# Versorgungseinheit_v2.net
KiCad netlist of a schematic drawn in EAGLE
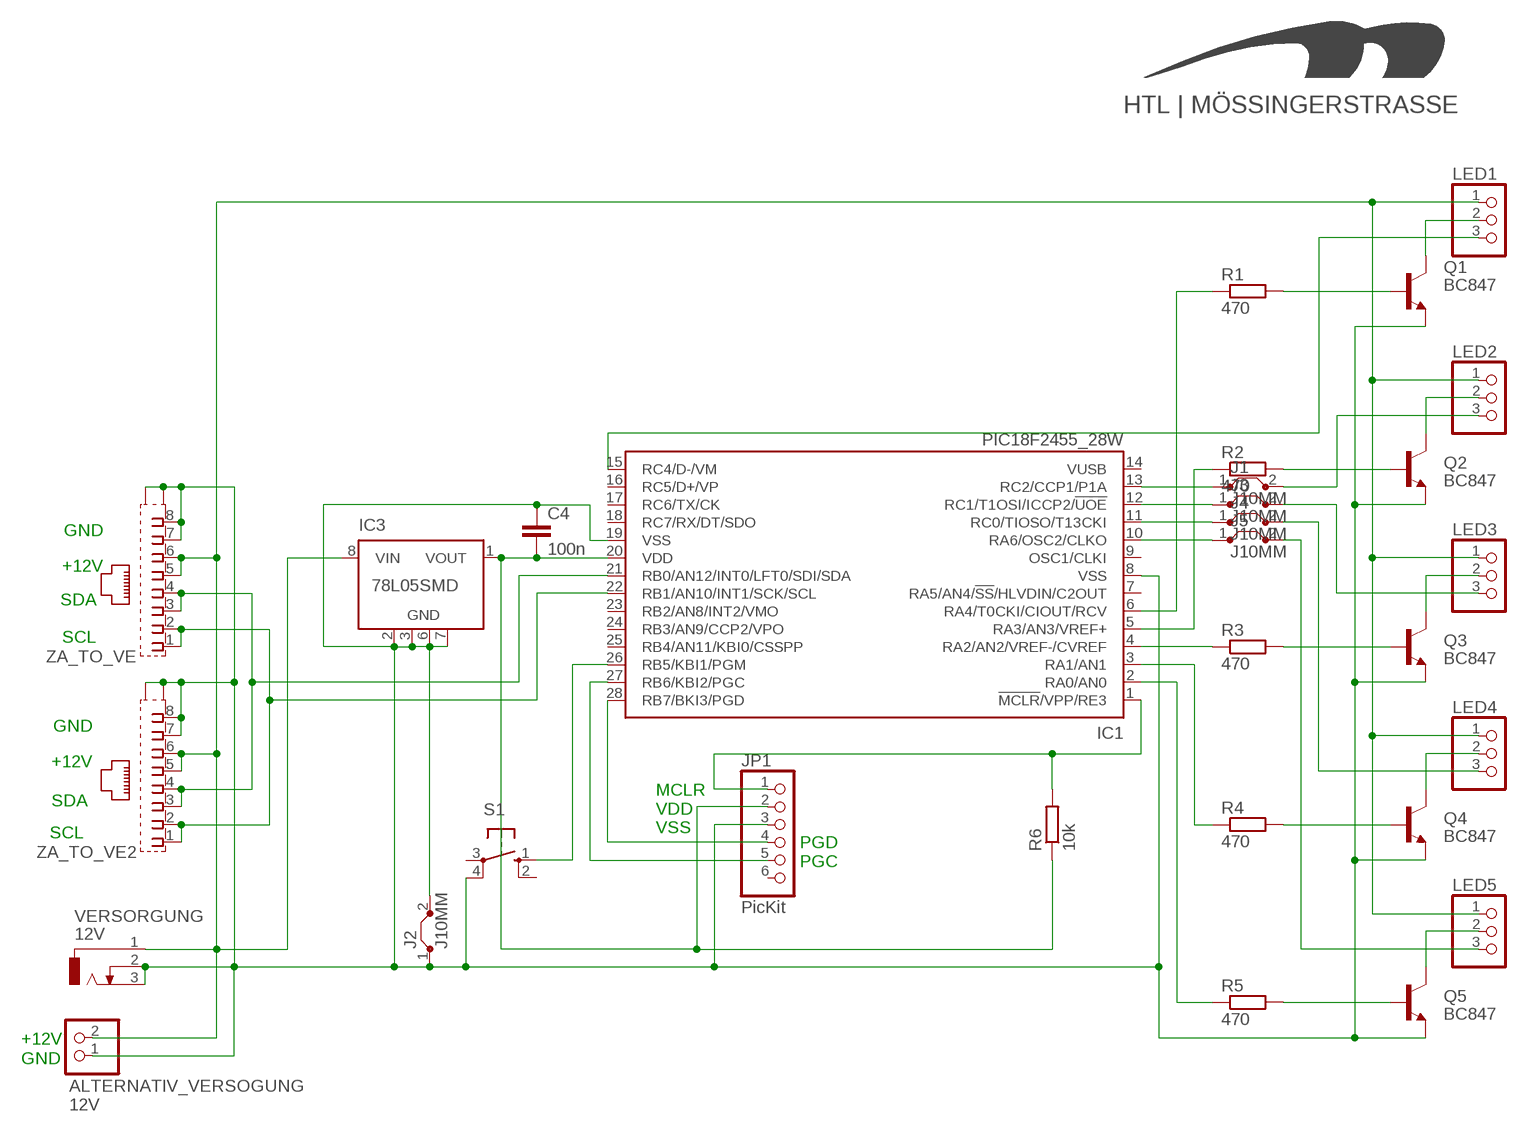
[diagram p0: schematic, sheet 1]

(export (version "E")
  (design (tool "Eeschema 10.0.6"))
  (components
    (comp (ref "ALTERNATIV_VERSOGUNG")
      (value "12V")
      (footprint "eagle-import:1X02")
      (libsource (lib "eagle-import") (part "PINHD-1X2"))
    )
    (comp (ref "C4")
      (value "100n")
      (footprint "eagle-import:C1206")
      (libsource (lib "eagle-import") (part "C-EUC1206"))
    )
    (comp (ref "IC1")
      (value "PIC18F2455_28W")
      (footprint "eagle-import:SO28W")
      (fields (field (name "MF") "MICROCHIP") (field (name "MPN") "PIC18F2455-I/SO"))
      (libsource (lib "eagle-import") (part "PIC18F2_28W455"))
    )
    (comp (ref "IC3")
      (value "78L05SMD")
      (footprint "eagle-import:SO08")
      (libsource (lib "eagle-import") (part "78LSMD05"))
    )
    (comp (ref "J1")
      (value "J10MM")
      (footprint "eagle-import:10")
      (libsource (lib "eagle-import") (part "J10MM"))
    )
    (comp (ref "J2")
      (value "J10MM")
      (footprint "eagle-import:10")
      (libsource (lib "eagle-import") (part "J10MM"))
    )
    (comp (ref "J3")
      (value "J10MM")
      (footprint "eagle-import:10")
      (libsource (lib "eagle-import") (part "J10MM"))
    )
    (comp (ref "J4")
      (value "J10MM")
      (footprint "eagle-import:10")
      (libsource (lib "eagle-import") (part "J10MM"))
    )
    (comp (ref "J5")
      (value "J10MM")
      (footprint "eagle-import:10")
      (libsource (lib "eagle-import") (part "J10MM"))
    )
    (comp (ref "JP1")
      (value "PicKit")
      (footprint "eagle-import:1X06")
      (libsource (lib "eagle-import") (part "PINHD-1X6"))
    )
    (comp (ref "LED1")
      (value "PINHD-1X3")
      (footprint "eagle-import:1X03")
      (libsource (lib "eagle-import") (part "PINHD-1X3"))
    )
    (comp (ref "LED2")
      (value "PINHD-1X3")
      (footprint "eagle-import:1X03")
      (libsource (lib "eagle-import") (part "PINHD-1X3"))
    )
    (comp (ref "LED3")
      (value "PINHD-1X3")
      (footprint "eagle-import:1X03")
      (libsource (lib "eagle-import") (part "PINHD-1X3"))
    )
    (comp (ref "LED4")
      (value "PINHD-1X3")
      (footprint "eagle-import:1X03")
      (libsource (lib "eagle-import") (part "PINHD-1X3"))
    )
    (comp (ref "LED5")
      (value "PINHD-1X3")
      (footprint "eagle-import:1X03")
      (libsource (lib "eagle-import") (part "PINHD-1X3"))
    )
    (comp (ref "Q1")
      (value "BC847")
      (footprint "eagle-import:SOT23")
      (libsource (lib "eagle-import") (part "BC847"))
    )
    (comp (ref "Q2")
      (value "BC847")
      (footprint "eagle-import:SOT23")
      (libsource (lib "eagle-import") (part "BC847"))
    )
    (comp (ref "Q3")
      (value "BC847")
      (footprint "eagle-import:SOT23")
      (libsource (lib "eagle-import") (part "BC847"))
    )
    (comp (ref "Q4")
      (value "BC847")
      (footprint "eagle-import:SOT23")
      (libsource (lib "eagle-import") (part "BC847"))
    )
    (comp (ref "Q5")
      (value "BC847")
      (footprint "eagle-import:SOT23")
      (libsource (lib "eagle-import") (part "BC847"))
    )
    (comp (ref "R1")
      (value "470")
      (footprint "eagle-import:R1206")
      (libsource (lib "eagle-import") (part "R-EU_R1206"))
    )
    (comp (ref "R2")
      (value "470")
      (footprint "eagle-import:R1206")
      (libsource (lib "eagle-import") (part "R-EU_R1206"))
    )
    (comp (ref "R3")
      (value "470")
      (footprint "eagle-import:R1206")
      (libsource (lib "eagle-import") (part "R-EU_R1206"))
    )
    (comp (ref "R4")
      (value "470")
      (footprint "eagle-import:R1206")
      (libsource (lib "eagle-import") (part "R-EU_R1206"))
    )
    (comp (ref "R5")
      (value "470")
      (footprint "eagle-import:R1206")
      (libsource (lib "eagle-import") (part "R-EU_R1206"))
    )
    (comp (ref "R6")
      (value "10k")
      (footprint "eagle-import:R1206")
      (libsource (lib "eagle-import") (part "R-EU_R1206"))
    )
    (comp (ref "S1")
      (value "10-XX")
      (footprint "eagle-import:B3F-10XX")
      (fields (field (name "MPN") "B3F-1000"))
      (libsource (lib "eagle-import") (part "10-XX"))
    )
    (comp (ref "U$1")
      (value "HTL_LOGOBOTTOP_15MM")
      (footprint "eagle-import:LOGO_15")
      (libsource (lib "eagle-import") (part "HTL_LOGOBOTTOP_15MM"))
    )
    (comp (ref "VERSORGUNG")
      (value "12V")
      (footprint "eagle-import:DCJ0303")
      (libsource (lib "eagle-import") (part "DCJ0303"))
    )
    (comp (ref "ZA_TO_VE")
      (value "555141-1")
      (footprint "eagle-import:555153-1")
      (libsource (lib "eagle-import") (part "555141-1"))
    )
    (comp (ref "ZA_TO_VE2")
      (value "555141-1")
      (footprint "eagle-import:555153-1")
      (libsource (lib "eagle-import") (part "555141-1"))
    )
  )
  (nets
    (net (code "1") (name "Net-(IC1-RA0{slash}AN0)") (class "Default")
      (node (ref "IC1") (pin "2") (pinfunction "RA0/AN0_2") (pintype "bidirectional"))
      (node (ref "R5") (pin "1") (pinfunction "1_1") (pintype "passive"))
    )
    (net (code "2") (name "Net-(IC1-RA1{slash}AN1)") (class "Default")
      (node (ref "IC1") (pin "3") (pinfunction "RA1/AN1_3") (pintype "bidirectional"))
      (node (ref "R4") (pin "1") (pinfunction "1_1") (pintype "passive"))
    )
    (net (code "3") (name "Net-(IC1-RA2{slash}AN2{slash}VREF-{slash}CVREF)") (class "Default")
      (node (ref "IC1") (pin "4") (pinfunction "RA2/AN2/VREF-/CVREF_4") (pintype "bidirectional"))
      (node (ref "R3") (pin "1") (pinfunction "1_1") (pintype "passive"))
    )
    (net (code "4") (name "Net-(IC1-RA3{slash}AN3{slash}VREF+)") (class "Default")
      (node (ref "IC1") (pin "5") (pinfunction "RA3/AN3/VREF+_5") (pintype "bidirectional"))
      (node (ref "R2") (pin "1") (pinfunction "1_1") (pintype "passive"))
    )
    (net (code "5") (name "Net-(IC1-RA4{slash}T0CKI{slash}CIOUT{slash}RCV)") (class "Default")
      (node (ref "IC1") (pin "6") (pinfunction "RA4/T0CKI/CIOUT/RCV_6") (pintype "bidirectional"))
      (node (ref "R1") (pin "1") (pinfunction "1_1") (pintype "passive"))
    )
    (net (code "6") (name "Net-(IC1-RA6{slash}OSC2{slash}CLKO)") (class "Default")
      (node (ref "IC1") (pin "10") (pinfunction "RA6/OSC2/CLKO_10") (pintype "output"))
      (node (ref "J5") (pin "1") (pinfunction "1_1") (pintype "passive"))
    )
    (net (code "7") (name "Net-(IC1-RB0{slash}AN12{slash}INT0{slash}LFT0{slash}SDI{slash}SDA)") (class "Default")
      (node (ref "IC1") (pin "21") (pinfunction "RB0/AN12/INT0/LFT0/SDI/SDA_21") (pintype "bidirectional"))
      (node (ref "ZA_TO_VE") (pin "3") (pinfunction "3_3") (pintype "passive"))
      (node (ref "ZA_TO_VE") (pin "4") (pinfunction "4_4") (pintype "passive"))
      (node (ref "ZA_TO_VE2") (pin "3") (pinfunction "3_3") (pintype "passive"))
      (node (ref "ZA_TO_VE2") (pin "4") (pinfunction "4_4") (pintype "passive"))
    )
    (net (code "8") (name "Net-(IC1-RB1{slash}AN10{slash}INT1{slash}SCK{slash}SCL)") (class "Default")
      (node (ref "IC1") (pin "22") (pinfunction "RB1/AN10/INT1/SCK/SCL_22") (pintype "bidirectional"))
      (node (ref "ZA_TO_VE") (pin "1") (pinfunction "1_1") (pintype "passive"))
      (node (ref "ZA_TO_VE") (pin "2") (pinfunction "2_2") (pintype "passive"))
      (node (ref "ZA_TO_VE2") (pin "1") (pinfunction "1_1") (pintype "passive"))
      (node (ref "ZA_TO_VE2") (pin "2") (pinfunction "2_2") (pintype "passive"))
    )
    (net (code "9") (name "Net-(IC1-RB5{slash}KBI1{slash}PGM)") (class "Default")
      (node (ref "IC1") (pin "26") (pinfunction "RB5/KBI1/PGM_26") (pintype "bidirectional"))
      (node (ref "S1") (pin "1") (pinfunction "S_1") (pintype "passive"))
    )
    (net (code "10") (name "Net-(IC1-RB6{slash}KBI2{slash}PGC)") (class "Default")
      (node (ref "IC1") (pin "27") (pinfunction "RB6/KBI2/PGC_27") (pintype "bidirectional"))
      (node (ref "JP1") (pin "5") (pinfunction "5_5") (pintype "passive"))
    )
    (net (code "11") (name "Net-(IC1-RB7{slash}BKI3{slash}PGD)") (class "Default")
      (node (ref "IC1") (pin "28") (pinfunction "RB7/BKI3/PGD_28") (pintype "bidirectional"))
      (node (ref "JP1") (pin "4") (pinfunction "4_4") (pintype "passive"))
    )
    (net (code "12") (name "Net-(IC1-RC0{slash}TIOSO{slash}T13CKI)") (class "Default")
      (node (ref "IC1") (pin "11") (pinfunction "RC0/TIOSO/T13CKI_11") (pintype "bidirectional"))
      (node (ref "J4") (pin "1") (pinfunction "1_1") (pintype "passive"))
    )
    (net (code "13") (name "Net-(IC1-RC1{slash}T1OSI{slash}ICCP2{slash}~{UOE})") (class "Default")
      (node (ref "IC1") (pin "12") (pinfunction "RC1/T1OSI/ICCP2/~{UOE}_12") (pintype "bidirectional"))
      (node (ref "J3") (pin "1") (pinfunction "1_1") (pintype "passive"))
    )
    (net (code "14") (name "Net-(IC1-RC2{slash}CCP1{slash}P1A)") (class "Default")
      (node (ref "IC1") (pin "13") (pinfunction "RC2/CCP1/P1A_13") (pintype "bidirectional"))
      (node (ref "J1") (pin "1") (pinfunction "1_1") (pintype "passive"))
    )
    (net (code "15") (name "Net-(IC1-RC4{slash}D-{slash}VM)") (class "Default")
      (node (ref "IC1") (pin "15") (pinfunction "RC4/D-/VM_15") (pintype "bidirectional"))
      (node (ref "LED1") (pin "3") (pinfunction "3_3") (pintype "passive"))
    )
    (net (code "16") (name "Net-(IC1-VDD)") (class "Default")
      (node (ref "C4") (pin "2") (pinfunction "2_2") (pintype "passive"))
      (node (ref "IC1") (pin "20") (pinfunction "VDD_20") (pintype "power_in"))
      (node (ref "IC3") (pin "1") (pinfunction "VOUT_1") (pintype "output"))
      (node (ref "JP1") (pin "2") (pinfunction "2_2") (pintype "passive"))
      (node (ref "R6") (pin "1") (pinfunction "1_1") (pintype "passive"))
    )
    (net (code "17") (name "Net-(IC1-~{MCLR}{slash}VPP{slash}RE3)") (class "Default")
      (node (ref "IC1") (pin "1") (pinfunction "~{MCLR}/VPP/RE3_1") (pintype "input"))
      (node (ref "JP1") (pin "1") (pinfunction "1_1") (pintype "passive"))
      (node (ref "R6") (pin "2") (pinfunction "2_2") (pintype "passive"))
    )
    (net (code "18") (name "Net-(IC3A-VIN)") (class "Default")
      (node (ref "ALTERNATIV_VERSOGUNG") (pin "2") (pinfunction "2_2") (pintype "passive"))
      (node (ref "IC3") (pin "8") (pinfunction "VIN_8") (pintype "passive"))
      (node (ref "LED1") (pin "1") (pinfunction "1_1") (pintype "passive"))
      (node (ref "LED2") (pin "1") (pinfunction "1_1") (pintype "passive"))
      (node (ref "LED3") (pin "1") (pinfunction "1_1") (pintype "passive"))
      (node (ref "LED4") (pin "1") (pinfunction "1_1") (pintype "passive"))
      (node (ref "LED5") (pin "1") (pinfunction "1_1") (pintype "passive"))
      (node (ref "VERSORGUNG") (pin "1") (pinfunction "1_1") (pintype "passive"))
      (node (ref "ZA_TO_VE") (pin "5") (pinfunction "5_5") (pintype "passive"))
      (node (ref "ZA_TO_VE") (pin "6") (pinfunction "6_6") (pintype "passive"))
      (node (ref "ZA_TO_VE2") (pin "5") (pinfunction "5_5") (pintype "passive"))
      (node (ref "ZA_TO_VE2") (pin "6") (pinfunction "6_6") (pintype "passive"))
    )
    (net (code "19") (name "Net-(J1-Pad2)") (class "Default")
      (node (ref "J1") (pin "2") (pinfunction "2_2") (pintype "passive"))
      (node (ref "LED2") (pin "3") (pinfunction "3_3") (pintype "passive"))
    )
    (net (code "20") (name "Net-(J3-Pad2)") (class "Default")
      (node (ref "J3") (pin "2") (pinfunction "2_2") (pintype "passive"))
      (node (ref "LED3") (pin "3") (pinfunction "3_3") (pintype "passive"))
    )
    (net (code "21") (name "Net-(J4-Pad2)") (class "Default")
      (node (ref "J4") (pin "2") (pinfunction "2_2") (pintype "passive"))
      (node (ref "LED4") (pin "3") (pinfunction "3_3") (pintype "passive"))
    )
    (net (code "22") (name "Net-(J5-Pad2)") (class "Default")
      (node (ref "J5") (pin "2") (pinfunction "2_2") (pintype "passive"))
      (node (ref "LED5") (pin "3") (pinfunction "3_3") (pintype "passive"))
    )
    (net (code "23") (name "Net-(Q1-B)") (class "Default")
      (node (ref "Q1") (pin "1") (pinfunction "B_1") (pintype "passive"))
      (node (ref "R1") (pin "2") (pinfunction "2_2") (pintype "passive"))
    )
    (net (code "24") (name "Net-(Q1-C)") (class "Default")
      (node (ref "LED1") (pin "2") (pinfunction "2_2") (pintype "passive"))
      (node (ref "Q1") (pin "3") (pinfunction "C_3") (pintype "passive"))
    )
    (net (code "25") (name "Net-(Q1-E)") (class "Default")
      (node (ref "ALTERNATIV_VERSOGUNG") (pin "1") (pinfunction "1_1") (pintype "passive"))
      (node (ref "C4") (pin "1") (pinfunction "1_1") (pintype "passive"))
      (node (ref "IC1") (pin "19") (pinfunction "VSS_19") (pintype "power_in"))
      (node (ref "IC1") (pin "8") (pinfunction "VSS_8") (pintype "power_in"))
      (node (ref "IC3") (pin "2") (pinfunction "GND_2") (pintype "power_in"))
      (node (ref "IC3") (pin "3") (pinfunction "GND_3") (pintype "power_in"))
      (node (ref "IC3") (pin "6") (pinfunction "GND_6") (pintype "power_in"))
      (node (ref "IC3") (pin "7") (pinfunction "GND_7") (pintype "power_in"))
      (node (ref "J2") (pin "1") (pinfunction "1_1") (pintype "passive"))
      (node (ref "J2") (pin "2") (pinfunction "2_2") (pintype "passive"))
      (node (ref "JP1") (pin "3") (pinfunction "3_3") (pintype "passive"))
      (node (ref "Q1") (pin "2") (pinfunction "E_2") (pintype "passive"))
      (node (ref "Q2") (pin "2") (pinfunction "E_2") (pintype "passive"))
      (node (ref "Q3") (pin "2") (pinfunction "E_2") (pintype "passive"))
      (node (ref "Q4") (pin "2") (pinfunction "E_2") (pintype "passive"))
      (node (ref "Q5") (pin "2") (pinfunction "E_2") (pintype "passive"))
      (node (ref "S1") (pin "4") (pinfunction "P1_4") (pintype "passive"))
      (node (ref "VERSORGUNG") (pin "2") (pinfunction "2_2") (pintype "passive"))
      (node (ref "VERSORGUNG") (pin "3") (pinfunction "3_3") (pintype "passive"))
      (node (ref "ZA_TO_VE") (pin "7") (pinfunction "7_7") (pintype "passive"))
      (node (ref "ZA_TO_VE") (pin "8") (pinfunction "8_8") (pintype "passive"))
      (node (ref "ZA_TO_VE") (pin "G1") (pinfunction "S1_G1") (pintype "passive"))
      (node (ref "ZA_TO_VE") (pin "G2") (pinfunction "S2_G2") (pintype "passive"))
      (node (ref "ZA_TO_VE2") (pin "7") (pinfunction "7_7") (pintype "passive"))
      (node (ref "ZA_TO_VE2") (pin "8") (pinfunction "8_8") (pintype "passive"))
      (node (ref "ZA_TO_VE2") (pin "G1") (pinfunction "S1_G1") (pintype "passive"))
      (node (ref "ZA_TO_VE2") (pin "G2") (pinfunction "S2_G2") (pintype "passive"))
    )
    (net (code "26") (name "Net-(Q2-B)") (class "Default")
      (node (ref "Q2") (pin "1") (pinfunction "B_1") (pintype "passive"))
      (node (ref "R2") (pin "2") (pinfunction "2_2") (pintype "passive"))
    )
    (net (code "27") (name "Net-(Q2-C)") (class "Default")
      (node (ref "LED2") (pin "2") (pinfunction "2_2") (pintype "passive"))
      (node (ref "Q2") (pin "3") (pinfunction "C_3") (pintype "passive"))
    )
    (net (code "28") (name "Net-(Q3-B)") (class "Default")
      (node (ref "Q3") (pin "1") (pinfunction "B_1") (pintype "passive"))
      (node (ref "R3") (pin "2") (pinfunction "2_2") (pintype "passive"))
    )
    (net (code "29") (name "Net-(Q3-C)") (class "Default")
      (node (ref "LED3") (pin "2") (pinfunction "2_2") (pintype "passive"))
      (node (ref "Q3") (pin "3") (pinfunction "C_3") (pintype "passive"))
    )
    (net (code "30") (name "Net-(Q4-B)") (class "Default")
      (node (ref "Q4") (pin "1") (pinfunction "B_1") (pintype "passive"))
      (node (ref "R4") (pin "2") (pinfunction "2_2") (pintype "passive"))
    )
    (net (code "31") (name "Net-(Q4-C)") (class "Default")
      (node (ref "LED4") (pin "2") (pinfunction "2_2") (pintype "passive"))
      (node (ref "Q4") (pin "3") (pinfunction "C_3") (pintype "passive"))
    )
    (net (code "32") (name "Net-(Q5-B)") (class "Default")
      (node (ref "Q5") (pin "1") (pinfunction "B_1") (pintype "passive"))
      (node (ref "R5") (pin "2") (pinfunction "2_2") (pintype "passive"))
    )
    (net (code "33") (name "Net-(Q5-C)") (class "Default")
      (node (ref "LED5") (pin "2") (pinfunction "2_2") (pintype "passive"))
      (node (ref "Q5") (pin "3") (pinfunction "C_3") (pintype "passive"))
    )
    (net (code "34") (name "unconnected-(IC1-OSC1{slash}CLKI-Pad9)") (class "Default")
      (node (ref "IC1") (pin "9") (pinfunction "OSC1/CLKI_9") (pintype "input"))
    )
    (net (code "35") (name "unconnected-(IC1-RA5{slash}AN4{slash}~{SS}{slash}HLVDIN{slash}C2OUT-Pad7)") (class "Default")
      (node (ref "IC1") (pin "7") (pinfunction "RA5/AN4/~{SS}/HLVDIN/C2OUT_7") (pintype "bidirectional"))
    )
    (net (code "36") (name "unconnected-(IC1-RB2{slash}AN8{slash}INT2{slash}VMO-Pad23)") (class "Default")
      (node (ref "IC1") (pin "23") (pinfunction "RB2/AN8/INT2/VMO_23") (pintype "bidirectional"))
    )
    (net (code "37") (name "unconnected-(IC1-RB3{slash}AN9{slash}CCP2{slash}VPO-Pad24)") (class "Default")
      (node (ref "IC1") (pin "24") (pinfunction "RB3/AN9/CCP2/VPO_24") (pintype "bidirectional"))
    )
    (net (code "38") (name "unconnected-(IC1-RB4{slash}AN11{slash}KBI0{slash}CSSPP-Pad25)") (class "Default")
      (node (ref "IC1") (pin "25") (pinfunction "RB4/AN11/KBI0/CSSPP_25") (pintype "bidirectional"))
    )
    (net (code "39") (name "unconnected-(IC1-RC5{slash}D+{slash}VP-Pad16)") (class "Default")
      (node (ref "IC1") (pin "16") (pinfunction "RC5/D+/VP_16") (pintype "bidirectional"))
    )
    (net (code "40") (name "unconnected-(IC1-RC6{slash}TX{slash}CK-Pad17)") (class "Default")
      (node (ref "IC1") (pin "17") (pinfunction "RC6/TX/CK_17") (pintype "bidirectional"))
    )
    (net (code "41") (name "unconnected-(IC1-RC7{slash}RX{slash}DT{slash}SDO-Pad18)") (class "Default")
      (node (ref "IC1") (pin "18") (pinfunction "RC7/RX/DT/SDO_18") (pintype "bidirectional"))
    )
    (net (code "42") (name "unconnected-(IC1-VUSB-Pad14)") (class "Default")
      (node (ref "IC1") (pin "14") (pinfunction "VUSB_14") (pintype "bidirectional"))
    )
    (net (code "43") (name "unconnected-(JP1-Pad6)") (class "Default")
      (node (ref "JP1") (pin "6") (pinfunction "6_6") (pintype "passive"))
    )
    (net (code "44") (name "unconnected-(S1-P-Pad3)") (class "Default")
      (node (ref "S1") (pin "3") (pinfunction "P_3") (pintype "passive"))
    )
    (net (code "45") (name "unconnected-(S1-S1-Pad2)") (class "Default")
      (node (ref "S1") (pin "2") (pinfunction "S1_2") (pintype "passive"))
    )
  )
)
